# 150529-Sequencer_rev_04.net
KiCad netlist of a schematic drawn in EAGLE
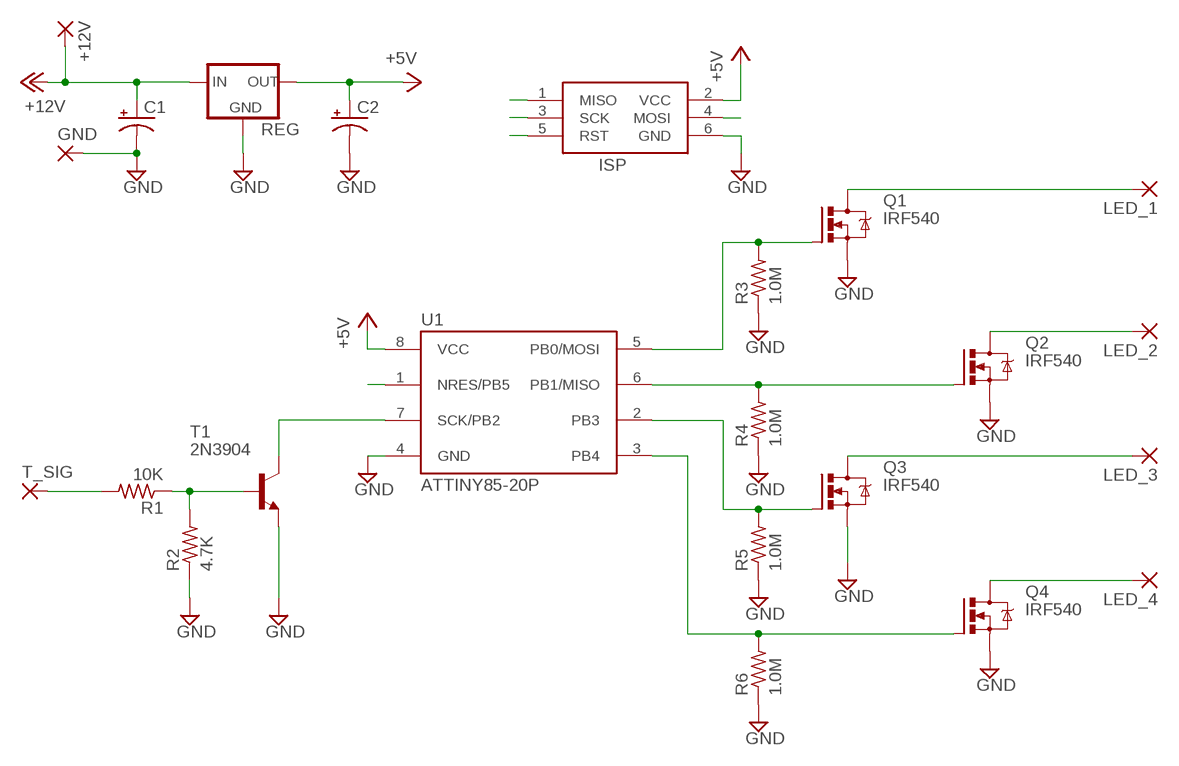
[diagram p0: schematic, sheet 1]

(export (version "E")
  (design (tool "Eeschema 10.0.6"))
  (components
    (comp (ref "+12V")
      (value "1,6/0,8")
      (footprint "eagle-import:1,6_0,8")
      (libsource (lib "eagle-import") (part "1,6/0,8"))
    )
    (comp (ref "C1")
      (value "CPOL-USE5-10.5")
      (footprint "eagle-import:E5-10,5")
      (libsource (lib "eagle-import") (part "CPOL-USE5-10.5"))
    )
    (comp (ref "C2")
      (value "CPOL-USE5-10.5")
      (footprint "eagle-import:E5-10,5")
      (libsource (lib "eagle-import") (part "CPOL-USE5-10.5"))
    )
    (comp (ref "GND")
      (value "1,6/0,8")
      (footprint "eagle-import:1,6_0,8")
      (libsource (lib "eagle-import") (part "1,6/0,8"))
    )
    (comp (ref "ISP")
      (value "AVRISP-6")
      (footprint "eagle-import:AVRISP")
      (libsource (lib "eagle-import") (part "AVRISP-6"))
    )
    (comp (ref "LED_1")
      (value "1,6/0,8")
      (footprint "eagle-import:1,6_0,8")
      (libsource (lib "eagle-import") (part "1,6/0,8"))
    )
    (comp (ref "LED_2")
      (value "1,6/0,8")
      (footprint "eagle-import:1,6_0,8")
      (libsource (lib "eagle-import") (part "1,6/0,8"))
    )
    (comp (ref "LED_3")
      (value "1,6/0,8")
      (footprint "eagle-import:1,6_0,8")
      (libsource (lib "eagle-import") (part "1,6/0,8"))
    )
    (comp (ref "LED_4")
      (value "1,6/0,8")
      (footprint "eagle-import:1,6_0,8")
      (libsource (lib "eagle-import") (part "1,6/0,8"))
    )
    (comp (ref "Q1")
      (value "IRF540")
      (footprint "eagle-import:TO220BV")
      (libsource (lib "eagle-import") (part "IRF540"))
    )
    (comp (ref "Q2")
      (value "IRF540")
      (footprint "eagle-import:TO220BV")
      (libsource (lib "eagle-import") (part "IRF540"))
    )
    (comp (ref "Q3")
      (value "IRF540")
      (footprint "eagle-import:TO220BV")
      (libsource (lib "eagle-import") (part "IRF540"))
    )
    (comp (ref "Q4")
      (value "IRF540")
      (footprint "eagle-import:TO220BV")
      (libsource (lib "eagle-import") (part "IRF540"))
    )
    (comp (ref "R1")
      (value "10K")
      (footprint "eagle-import:0207_2V")
      (libsource (lib "eagle-import") (part "R-US_0207/2V"))
    )
    (comp (ref "R2")
      (value "4.7K")
      (footprint "eagle-import:0207_2V")
      (libsource (lib "eagle-import") (part "R-US_0207/2V"))
    )
    (comp (ref "R3")
      (value "1.0M")
      (footprint "eagle-import:0207_2V")
      (libsource (lib "eagle-import") (part "R-US_0207/2V"))
    )
    (comp (ref "R4")
      (value "1.0M")
      (footprint "eagle-import:0207_2V")
      (libsource (lib "eagle-import") (part "R-US_0207/2V"))
    )
    (comp (ref "R5")
      (value "1.0M")
      (footprint "eagle-import:0207_2V")
      (libsource (lib "eagle-import") (part "R-US_0207/2V"))
    )
    (comp (ref "R6")
      (value "1.0M")
      (footprint "eagle-import:0207_2V")
      (libsource (lib "eagle-import") (part "R-US_0207/2V"))
    )
    (comp (ref "REG")
      (value "78XXS")
      (footprint "eagle-import:78XXS")
      (libsource (lib "eagle-import") (part "78XXS"))
    )
    (comp (ref "T1")
      (value "2N3904")
      (footprint "eagle-import:TO92")
      (libsource (lib "eagle-import") (part "2N3904"))
    )
    (comp (ref "T_SIG")
      (value "1,6/0,8")
      (footprint "eagle-import:1,6_0,8")
      (libsource (lib "eagle-import") (part "1,6/0,8"))
    )
    (comp (ref "U1")
      (value "ATTINY85-20P")
      (footprint "eagle-import:PDIP08_300MIL")
      (libsource (lib "eagle-import") (part "ATTINY85P-20"))
    )
  )
  (nets
    (net (code "1") (name "+5V") (class "Default")
      (node (ref "C2") (pin "+") (pinfunction "+_+") (pintype "passive"))
      (node (ref "ISP") (pin "2") (pinfunction "VCC_2") (pintype "power_in"))
      (node (ref "REG") (pin "OUT") (pinfunction "OUT_OUT") (pintype "passive"))
      (node (ref "U1") (pin "8") (pinfunction "VCC_8") (pintype "power_in"))
    )
    (net (code "2") (name "+12V") (class "Default")
      (node (ref "+12V") (pin "1") (pinfunction "P_1") (pintype "passive"))
      (node (ref "C1") (pin "+") (pinfunction "+_+") (pintype "passive"))
      (node (ref "REG") (pin "IN") (pinfunction "IN_IN") (pintype "input"))
    )
    (net (code "3") (name "/NRES{slash}PB5") (class "Default")
      (node (ref "ISP") (pin "5") (pinfunction "RST_5") (pintype "output"))
      (node (ref "U1") (pin "1") (pinfunction "NRES/PB5_1") (pintype "bidirectional"))
    )
    (net (code "4") (name "/PB0{slash}MOSI") (class "Default")
      (node (ref "ISP") (pin "4") (pinfunction "MOSI_4") (pintype "output"))
      (node (ref "Q1") (pin "G") (pinfunction "G_G") (pintype "passive"))
      (node (ref "R3") (pin "2") (pinfunction "2_2") (pintype "passive"))
      (node (ref "U1") (pin "5") (pinfunction "PB0/MOSI_5") (pintype "bidirectional"))
    )
    (net (code "5") (name "/PB1{slash}MISO") (class "Default")
      (node (ref "ISP") (pin "1") (pinfunction "MISO_1") (pintype "input"))
      (node (ref "Q2") (pin "G") (pinfunction "G_G") (pintype "passive"))
      (node (ref "R4") (pin "2") (pinfunction "2_2") (pintype "passive"))
      (node (ref "U1") (pin "6") (pinfunction "PB1/MISO_6") (pintype "bidirectional"))
    )
    (net (code "6") (name "/SCK{slash}PB2") (class "Default")
      (node (ref "ISP") (pin "3") (pinfunction "SCK_3") (pintype "output"))
      (node (ref "T1") (pin "1") (pinfunction "C_1") (pintype "passive"))
      (node (ref "U1") (pin "7") (pinfunction "SCK/PB2_7") (pintype "bidirectional"))
    )
    (net (code "7") (name "GND") (class "Default")
      (node (ref "C1") (pin "-") (pinfunction "-_-") (pintype "passive"))
      (node (ref "C2") (pin "-") (pinfunction "-_-") (pintype "passive"))
      (node (ref "GND") (pin "1") (pinfunction "P_1") (pintype "passive"))
      (node (ref "ISP") (pin "6") (pinfunction "GND_6") (pintype "power_in"))
      (node (ref "Q1") (pin "S") (pinfunction "S_S") (pintype "passive"))
      (node (ref "Q2") (pin "S") (pinfunction "S_S") (pintype "passive"))
      (node (ref "Q3") (pin "S") (pinfunction "S_S") (pintype "passive"))
      (node (ref "Q4") (pin "S") (pinfunction "S_S") (pintype "passive"))
      (node (ref "R2") (pin "1") (pinfunction "1_1") (pintype "passive"))
      (node (ref "R3") (pin "1") (pinfunction "1_1") (pintype "passive"))
      (node (ref "R4") (pin "1") (pinfunction "1_1") (pintype "passive"))
      (node (ref "R5") (pin "1") (pinfunction "1_1") (pintype "passive"))
      (node (ref "R6") (pin "1") (pinfunction "1_1") (pintype "passive"))
      (node (ref "REG") (pin "GND") (pinfunction "GND_GND") (pintype "input"))
      (node (ref "T1") (pin "3") (pinfunction "E_3") (pintype "passive"))
      (node (ref "U1") (pin "4") (pinfunction "GND_4") (pintype "power_in"))
    )
    (net (code "8") (name "Net-(LED_1-P)") (class "Default")
      (node (ref "LED_1") (pin "1") (pinfunction "P_1") (pintype "passive"))
      (node (ref "Q1") (pin "D") (pinfunction "D_D") (pintype "passive"))
    )
    (net (code "9") (name "Net-(LED_2-P)") (class "Default")
      (node (ref "LED_2") (pin "1") (pinfunction "P_1") (pintype "passive"))
      (node (ref "Q2") (pin "D") (pinfunction "D_D") (pintype "passive"))
    )
    (net (code "10") (name "Net-(LED_3-P)") (class "Default")
      (node (ref "LED_3") (pin "1") (pinfunction "P_1") (pintype "passive"))
      (node (ref "Q3") (pin "D") (pinfunction "D_D") (pintype "passive"))
    )
    (net (code "11") (name "Net-(LED_4-P)") (class "Default")
      (node (ref "LED_4") (pin "1") (pinfunction "P_1") (pintype "passive"))
      (node (ref "Q4") (pin "D") (pinfunction "D_D") (pintype "passive"))
    )
    (net (code "12") (name "Net-(T1-B)") (class "Default")
      (node (ref "R1") (pin "1") (pinfunction "1_1") (pintype "passive"))
      (node (ref "R2") (pin "2") (pinfunction "2_2") (pintype "passive"))
      (node (ref "T1") (pin "2") (pinfunction "B_2") (pintype "passive"))
    )
    (net (code "13") (name "Net-(T_SIG-P)") (class "Default")
      (node (ref "R1") (pin "2") (pinfunction "2_2") (pintype "passive"))
      (node (ref "T_SIG") (pin "1") (pinfunction "P_1") (pintype "passive"))
    )
    (net (code "14") (name "Net-(U1-PB3)") (class "Default")
      (node (ref "Q3") (pin "G") (pinfunction "G_G") (pintype "passive"))
      (node (ref "R5") (pin "2") (pinfunction "2_2") (pintype "passive"))
      (node (ref "U1") (pin "2") (pinfunction "PB3_2") (pintype "bidirectional"))
    )
    (net (code "15") (name "Net-(U1-PB4)") (class "Default")
      (node (ref "Q4") (pin "G") (pinfunction "G_G") (pintype "passive"))
      (node (ref "R6") (pin "2") (pinfunction "2_2") (pintype "passive"))
      (node (ref "U1") (pin "3") (pinfunction "PB4_3") (pintype "bidirectional"))
    )
  )
)
